# 2T.net
KiCad netlist of a schematic drawn in Altium Designer
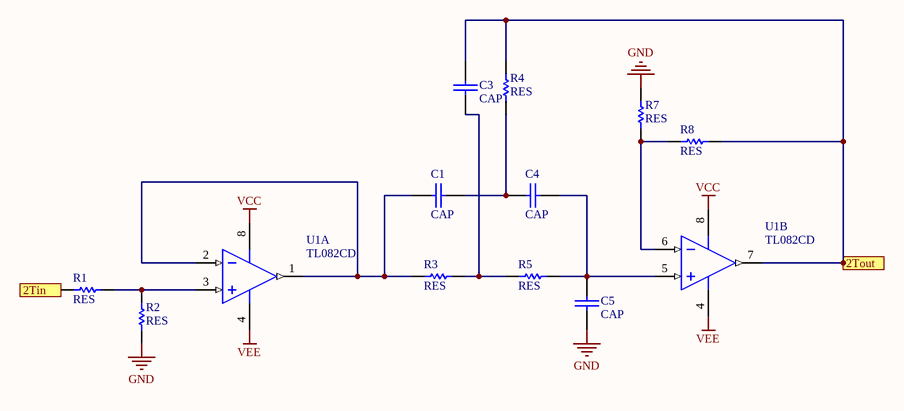
[diagram p0: 2T.SchDoc]

(export (version "E")
  (design (tool "Eeschema 10.0.6"))
  (components
    (comp (ref "C1") (value "CAP") (footprint "1206") (libsource (lib "LIBEBAL") (part "CAP")))
    (comp (ref "C3") (value "CAP") (footprint "1206") (libsource (lib "LIBEBAL") (part "CAP")))
    (comp (ref "C4") (value "CAP") (footprint "1206") (libsource (lib "LIBEBAL") (part "CAP")))
    (comp (ref "C5") (value "CAP") (footprint "1206") (libsource (lib "LIBEBAL") (part "CAP")))
    (comp (ref "R1") (value "RES") (footprint "1206") (libsource (lib "LIBEBAL") (part "RES")))
    (comp (ref "R2") (value "RES") (footprint "1206") (libsource (lib "LIBEBAL") (part "RES")))
    (comp (ref "R3") (value "RES") (footprint "1206") (libsource (lib "LIBEBAL") (part "RES")))
    (comp (ref "R4") (value "RES") (footprint "1206") (libsource (lib "LIBEBAL") (part "RES")))
    (comp (ref "R5") (value "RES") (footprint "1206") (libsource (lib "LIBEBAL") (part "RES")))
    (comp (ref "R7") (value "RES") (footprint "1206") (libsource (lib "LIBEBAL") (part "RES")))
    (comp (ref "R8") (value "RES") (footprint "1206") (libsource (lib "LIBEBAL") (part "RES")))
    (comp (ref "U1")
      (value "TL082CD")
      (footprint "TI-D8_M")
      (fields (field (name "MANUFACTURER") "Texas Instruments"))
      (libsource (lib "TI Amplifiers and Linear Operational Amplifier General Purpose") (part "TL082CD"))
    )
  )
  (nets
    (net (code "1") (name "/2Tin") (class "Default")
      (node (ref "R1") (pin "1") (pinfunction "1_1") (pintype "passive"))
    )
    (net (code "2") (name "/2Tout") (class "Default")
      (node (ref "C3") (pin "2") (pinfunction "2_2") (pintype "passive"))
      (node (ref "R4") (pin "2") (pinfunction "2_2") (pintype "passive"))
      (node (ref "R8") (pin "1") (pinfunction "1_1") (pintype "passive"))
      (node (ref "U1") (pin "7") (pinfunction "OUT2_7") (pintype "output"))
    )
    (net (code "3") (name "GND") (class "Default")
      (node (ref "C5") (pin "1") (pinfunction "1_1") (pintype "passive"))
      (node (ref "R2") (pin "1") (pinfunction "1_1") (pintype "passive"))
      (node (ref "R7") (pin "2") (pinfunction "2_2") (pintype "passive"))
    )
    (net (code "4") (name "Net-(C1-Pad2)") (class "Default")
      (node (ref "C1") (pin "2") (pinfunction "2_2") (pintype "passive"))
      (node (ref "C4") (pin "1") (pinfunction "1_1") (pintype "passive"))
      (node (ref "R4") (pin "1") (pinfunction "1_1") (pintype "passive"))
    )
    (net (code "5") (name "Net-(C3-Pad1)") (class "Default")
      (node (ref "C3") (pin "1") (pinfunction "1_1") (pintype "passive"))
      (node (ref "R3") (pin "2") (pinfunction "2_2") (pintype "passive"))
      (node (ref "R5") (pin "1") (pinfunction "1_1") (pintype "passive"))
    )
    (net (code "6") (name "Net-(U1A-IN1+)") (class "Default")
      (node (ref "R1") (pin "2") (pinfunction "2_2") (pintype "passive"))
      (node (ref "R2") (pin "2") (pinfunction "2_2") (pintype "passive"))
      (node (ref "U1") (pin "3") (pinfunction "IN1+_3") (pintype "input"))
    )
    (net (code "7") (name "Net-(U1A-IN1-)") (class "Default")
      (node (ref "C1") (pin "1") (pinfunction "1_1") (pintype "passive"))
      (node (ref "R3") (pin "1") (pinfunction "1_1") (pintype "passive"))
      (node (ref "U1") (pin "1") (pinfunction "OUT1_1") (pintype "output"))
      (node (ref "U1") (pin "2") (pinfunction "IN1-_2") (pintype "input"))
    )
    (net (code "8") (name "Net-(U1B-IN2+)") (class "Default")
      (node (ref "C4") (pin "2") (pinfunction "2_2") (pintype "passive"))
      (node (ref "C5") (pin "2") (pinfunction "2_2") (pintype "passive"))
      (node (ref "R5") (pin "2") (pinfunction "2_2") (pintype "passive"))
      (node (ref "U1") (pin "5") (pinfunction "IN2+_5") (pintype "input"))
    )
    (net (code "9") (name "Net-(U1B-IN2-)") (class "Default")
      (node (ref "R7") (pin "1") (pinfunction "1_1") (pintype "passive"))
      (node (ref "R8") (pin "2") (pinfunction "2_2") (pintype "passive"))
      (node (ref "U1") (pin "6") (pinfunction "IN2-_6") (pintype "input"))
    )
    (net (code "10") (name "VCC") (class "Default")
      (node (ref "U1") (pin "8") (pinfunction "VCC+_8") (pintype "power_in"))
    )
    (net (code "11") (name "VEE") (class "Default")
      (node (ref "U1") (pin "4") (pinfunction "VCC-_4") (pintype "power_in"))
    )
  )
)
